# STM32G473RET6_PINOUT.net
KiCad netlist of a schematic drawn in Altium Designer
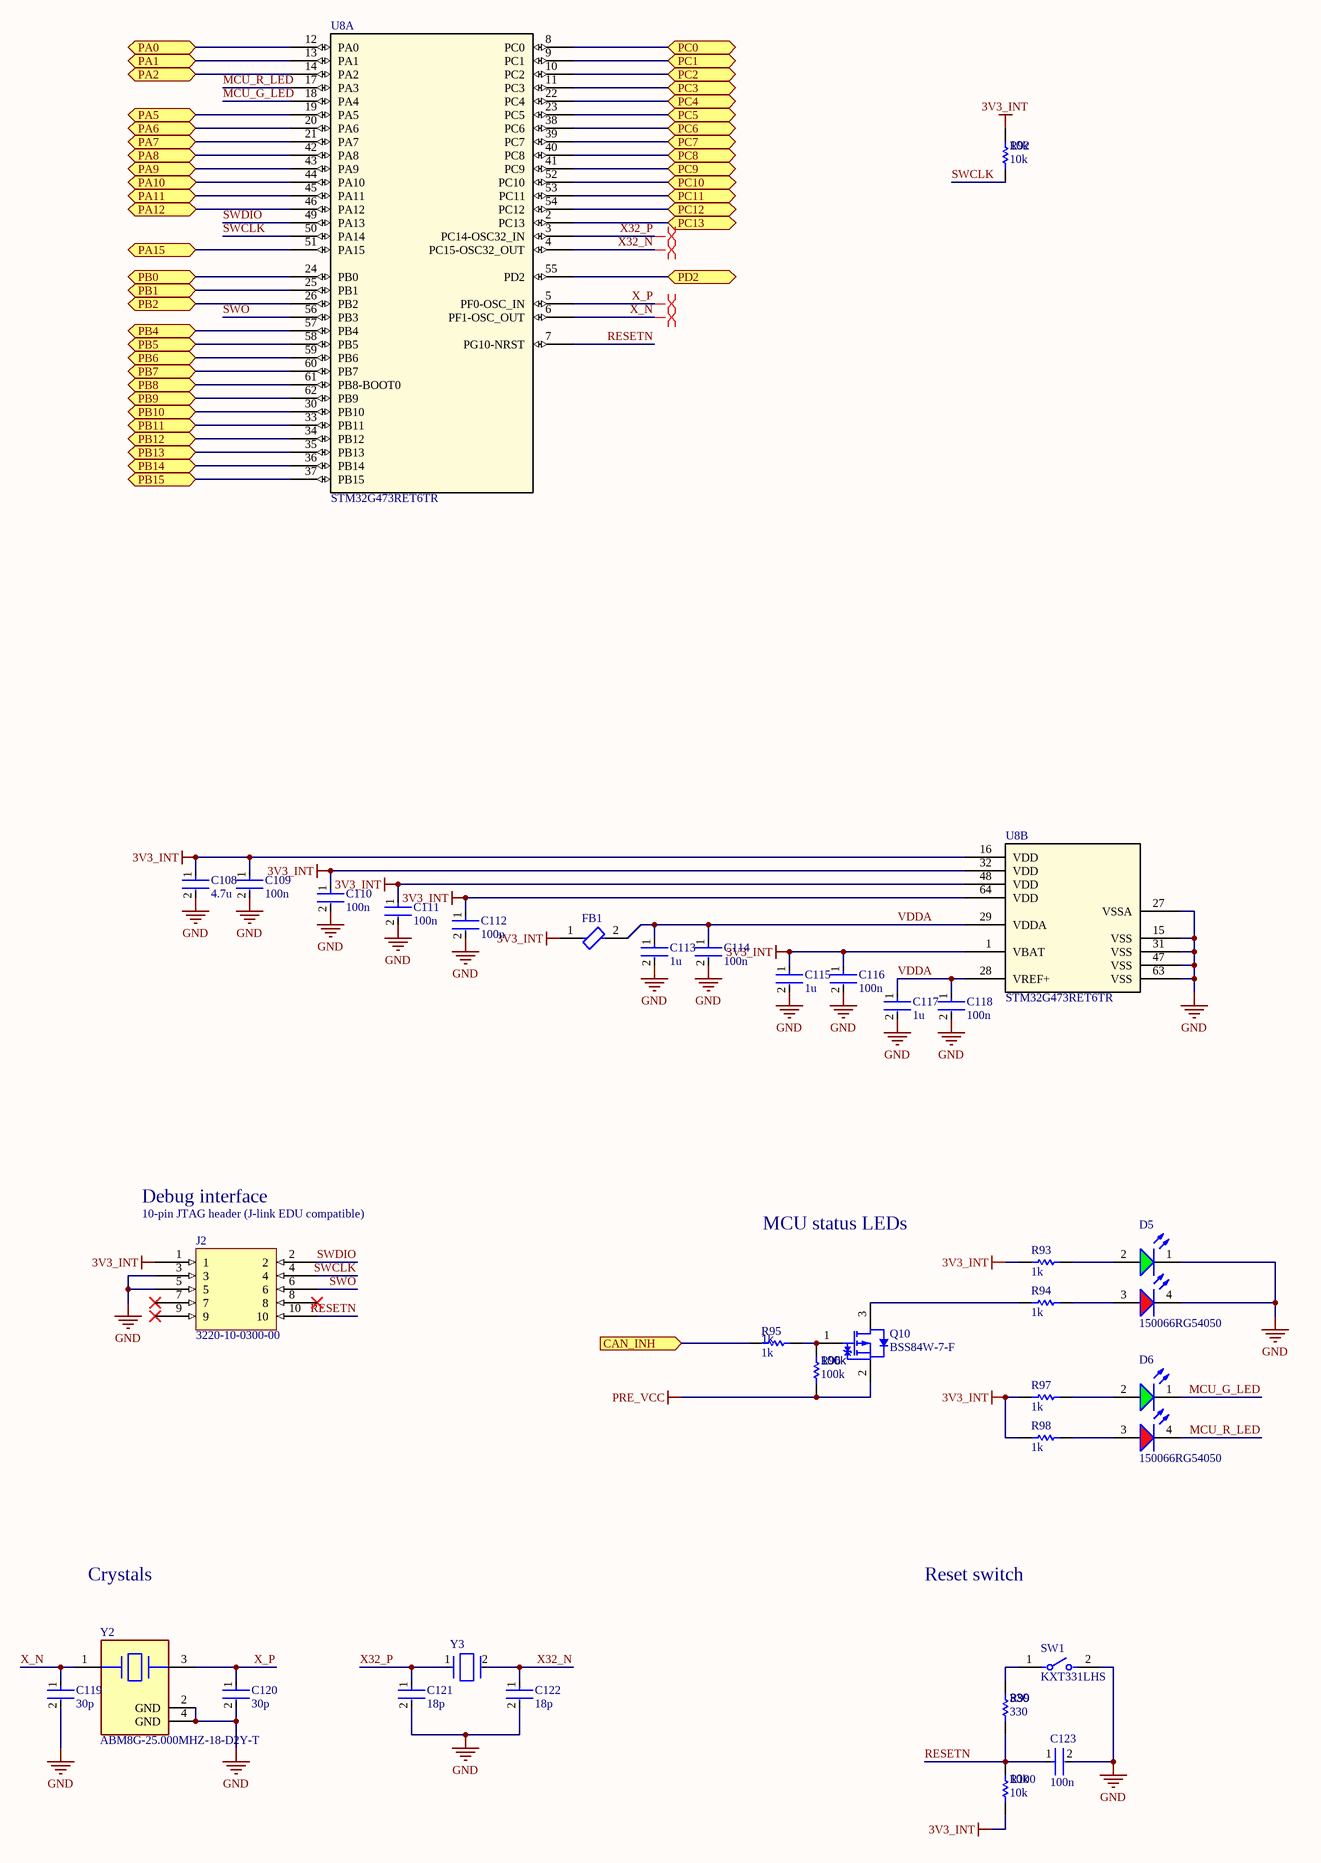
[diagram p0: STM32G473RET6_PINOUT.SchDoc]

(export (version "E")
  (design (tool "Eeschema 10.0.6"))
  (components
    (comp (ref "C108")
      (value "4.7u")
      (footprint "FP-0402-L_1_0_0_05-W_0_5-IPC_A")
      (description "LARGE PADS, 0402 CAP, CHANGE COMMENT TO MATCH REAL P/N")
      (libsource (lib "Space Concordia") (part "b4654b650e69147ec39a6b967a45e02"))
    )
    (comp (ref "C109")
      (value "100n")
      (footprint "FP-0402-L_1_0_0_05-W_0_5-IPC_A")
      (description "LARGE PADS, 0402 CAP, CHANGE COMMENT TO MATCH REAL P/N")
      (libsource (lib "Space Concordia") (part "b4654b650e69147ec39a6b967a45e02"))
    )
    (comp (ref "C110")
      (value "100n")
      (footprint "FP-0402-L_1_0_0_05-W_0_5-IPC_A")
      (description "LARGE PADS, 0402 CAP, CHANGE COMMENT TO MATCH REAL P/N")
      (libsource (lib "Space Concordia") (part "b4654b650e69147ec39a6b967a45e02"))
    )
    (comp (ref "C111")
      (value "100n")
      (footprint "FP-0402-L_1_0_0_05-W_0_5-IPC_A")
      (description "LARGE PADS, 0402 CAP, CHANGE COMMENT TO MATCH REAL P/N")
      (libsource (lib "Space Concordia") (part "b4654b650e69147ec39a6b967a45e02"))
    )
    (comp (ref "C112")
      (value "100n")
      (footprint "FP-0402-L_1_0_0_05-W_0_5-IPC_A")
      (description "LARGE PADS, 0402 CAP, CHANGE COMMENT TO MATCH REAL P/N")
      (libsource (lib "Space Concordia") (part "b4654b650e69147ec39a6b967a45e02"))
    )
    (comp (ref "C113")
      (value "1u")
      (footprint "FP-0402-L_1_0_0_05-W_0_5-IPC_A")
      (description "LARGE PADS, 0402 CAP, CHANGE COMMENT TO MATCH REAL P/N")
      (libsource (lib "Space Concordia") (part "b4654b650e69147ec39a6b967a45e02"))
    )
    (comp (ref "C114")
      (value "100n")
      (footprint "FP-0402-L_1_0_0_05-W_0_5-IPC_A")
      (description "LARGE PADS, 0402 CAP, CHANGE COMMENT TO MATCH REAL P/N")
      (libsource (lib "Space Concordia") (part "b4654b650e69147ec39a6b967a45e02"))
    )
    (comp (ref "C115")
      (value "1u")
      (footprint "FP-0402-L_1_0_0_05-W_0_5-IPC_A")
      (description "LARGE PADS, 0402 CAP, CHANGE COMMENT TO MATCH REAL P/N")
      (libsource (lib "Space Concordia") (part "b4654b650e69147ec39a6b967a45e02"))
    )
    (comp (ref "C116")
      (value "100n")
      (footprint "FP-0402-L_1_0_0_05-W_0_5-IPC_A")
      (description "LARGE PADS, 0402 CAP, CHANGE COMMENT TO MATCH REAL P/N")
      (libsource (lib "Space Concordia") (part "b4654b650e69147ec39a6b967a45e02"))
    )
    (comp (ref "C117")
      (value "1u")
      (footprint "FP-0402-L_1_0_0_05-W_0_5-IPC_A")
      (description "LARGE PADS, 0402 CAP, CHANGE COMMENT TO MATCH REAL P/N")
      (libsource (lib "Space Concordia") (part "b4654b650e69147ec39a6b967a45e02"))
    )
    (comp (ref "C118")
      (value "100n")
      (footprint "FP-0402-L_1_0_0_05-W_0_5-IPC_A")
      (description "LARGE PADS, 0402 CAP, CHANGE COMMENT TO MATCH REAL P/N")
      (libsource (lib "Space Concordia") (part "b4654b650e69147ec39a6b967a45e02"))
    )
    (comp (ref "C119")
      (value "30p")
      (footprint "FP-0402-L_1_0_0_05-W_0_5-IPC_A")
      (description "LARGE PADS, 0402 CAP, CHANGE COMMENT TO MATCH REAL P/N")
      (libsource (lib "Space Concordia") (part "b4654b650e69147ec39a6b967a45e02"))
    )
    (comp (ref "C120")
      (value "30p")
      (footprint "FP-0402-L_1_0_0_05-W_0_5-IPC_A")
      (description "LARGE PADS, 0402 CAP, CHANGE COMMENT TO MATCH REAL P/N")
      (libsource (lib "Space Concordia") (part "b4654b650e69147ec39a6b967a45e02"))
    )
    (comp (ref "C121")
      (value "18p")
      (footprint "FP-0402-L_1_0_0_05-W_0_5-IPC_A")
      (description "LARGE PADS, 0402 CAP, CHANGE COMMENT TO MATCH REAL P/N")
      (libsource (lib "Space Concordia") (part "b4654b650e69147ec39a6b967a45e02"))
    )
    (comp (ref "C122")
      (value "18p")
      (footprint "FP-0402-L_1_0_0_05-W_0_5-IPC_A")
      (description "LARGE PADS, 0402 CAP, CHANGE COMMENT TO MATCH REAL P/N")
      (libsource (lib "Space Concordia") (part "b4654b650e69147ec39a6b967a45e02"))
    )
    (comp (ref "C123")
      (value "100n")
      (footprint "FP-0402-L_1_0_0_05-W_0_5-IPC_A")
      (description "LARGE PADS, 0402 CAP, CHANGE COMMENT TO MATCH REAL P/N")
      (libsource (lib "Space Concordia") (part "b4654b650e69147ec39a6b967a45e02"))
    )
    (comp (ref "D5")
      (value "150066RG54050")
      (footprint "WL-SBCD_0606")
      (description "Led, Red/Grn, 180Mcd/230Mcd, 624Nm/525Nm Rohs Compliant: Yes")
      (fields (field (name "SOURCE") "rgled.SchLib"))
      (libsource (lib "Space Concordia") (part "CMP-004-00034-2"))
    )
    (comp (ref "D6")
      (value "150066RG54050")
      (footprint "WL-SBCD_0606")
      (description "Led, Red/Grn, 180Mcd/230Mcd, 624Nm/525Nm Rohs Compliant: Yes")
      (fields (field (name "SOURCE") "rgled.SchLib"))
      (libsource (lib "Space Concordia") (part "CMP-004-00034-2"))
    )
    (comp (ref "FB1")
      (value "BLM15PX601SN1D")
      (footprint "FP-BLM15-0_05-MFG")
      (description "Chip Ferrite Bead, 0402, 600Ω @ 100MHz, 0.23Ω, 25%, 900mA")
      (fields (field (name "TOLERANCE") "25%"))
      (libsource (lib "Altium Content Vault") (part "5f30dd21d616792df468990f7003faa"))
    )
    (comp (ref "J2")
      (value "3220-10-0300-00")
      (footprint "3220-10-0300-00-Footprint-1")
      (description "CONN HEADER SMD 10POS 1.27MM")
      (libsource (lib "Space Concordia") (part "3220-10-0300-00"))
    )
    (comp (ref "Q10")
      (value "BSS84W-7-F")
      (footprint "DIOD-SOT323-3_V")
      (fields (field (name "MANUFACTURER") "Diodes Inc"))
      (libsource (lib "Altium Content Vault") (part "PEMOS-GSD-3_C"))
    )
    (comp (ref "R92")
      (value "10k")
      (footprint "R0603B")
      (description "Resistor")
      (fields (field (name "ALTIUM_VALUE") "10k"))
      (libsource (lib "Space Concordia") (part "Resistor"))
    )
    (comp (ref "R93")
      (value "1k")
      (footprint "R0603B")
      (description "Resistor")
      (libsource (lib "Space Concordia") (part "Resistor"))
    )
    (comp (ref "R94")
      (value "1k")
      (footprint "R0603B")
      (description "Resistor")
      (libsource (lib "Space Concordia") (part "Resistor"))
    )
    (comp (ref "R95")
      (value "1k")
      (footprint "R0603B")
      (description "Resistor")
      (fields (field (name "ALTIUM_VALUE") "1k"))
      (libsource (lib "Space Concordia") (part "Resistor"))
    )
    (comp (ref "R96")
      (value "100k")
      (footprint "R0603B")
      (description "Resistor")
      (fields (field (name "ALTIUM_VALUE") "100k"))
      (libsource (lib "Space Concordia") (part "Resistor"))
    )
    (comp (ref "R97")
      (value "1k")
      (footprint "R0603B")
      (description "Resistor")
      (libsource (lib "Space Concordia") (part "Resistor"))
    )
    (comp (ref "R98")
      (value "1k")
      (footprint "R0603B")
      (description "Resistor")
      (libsource (lib "Space Concordia") (part "Resistor"))
    )
    (comp (ref "R99")
      (value "330")
      (footprint "R0603B")
      (description "Resistor")
      (fields (field (name "ALTIUM_VALUE") "330"))
      (libsource (lib "Space Concordia") (part "Resistor"))
    )
    (comp (ref "R100")
      (value "10k")
      (footprint "R0603B")
      (description "Resistor")
      (fields (field (name "ALTIUM_VALUE") "10k"))
      (libsource (lib "Space Concordia") (part "Resistor"))
    )
    (comp (ref "SW1")
      (value "KXT331LHS")
      (footprint "FP-KXT331LHS-MFG")
      (description "SWITCH TACTILE SPST-NO 0.02A 15V")
      (libsource (lib "Altium Content Vault") (part "bb27bde45df87f1f469753f287ef5ae"))
    )
    (comp (ref "U8")
      (value "STM32G473RET6TR")
      (footprint "STM32G473RET6TR-Footprint-1")
      (description "MCU 32-Bit STM32 ARM Cortex-M4 RISC 512KB Flash 1.71V to 3.6V 64-Pin LQFP T/R")
      (libsource (lib "Space Concordia") (part "STM32G473RET6TR"))
    )
    (comp (ref "Y2")
      (value "ABM8G-25.000MHZ-18-D2Y-T")
      (footprint "FP-ABM8G-MFG")
      (description "Crystal 25MHz ±20ppm (Tol) ±30ppm (Stability) 18pF FUND 60Ω 4-Pin SMD T/R")
      (fields (field (name "TOLERANCE") "20ppm"))
      (libsource (lib "Altium Content Vault") (part "48e526d86b7f2615d98721063c72f49"))
    )
    (comp (ref "Y3")
      (value "ECS-.327-12.5-1210-TR")
      (footprint "FP-ECX-1210-MFG")
      (description "CRYSTAL 32.7680KHZ 12.5PF SMD")
      (fields
        (field (name "OCTOPART") "https://octopart.com/ecs-.327-12.5-1210-tr-ecs+international-81221340")
        (field (name "TOLERANCE") "20ppm")
      )
      (libsource (lib "Altium Content Vault") (part "99724985039315a44fd0d1401b84e49"))
    )
  )
  (nets
    (net (code "1") (name "/CAN_INH") (class "Default")
      (node (ref "R95") (pin "2") (pinfunction "2_2") (pintype "passive"))
    )
    (net (code "2") (name "/MCU_G_LED") (class "Default")
      (node (ref "D6") (pin "1") (pinfunction "K_1") (pintype "passive"))
      (node (ref "U8") (pin "18") (pinfunction "PA4_18") (pintype "bidirectional"))
    )
    (net (code "3") (name "/MCU_R_LED") (class "Default")
      (node (ref "D6") (pin "4") (pinfunction "K_4") (pintype "passive"))
      (node (ref "U8") (pin "17") (pinfunction "PA3_17") (pintype "bidirectional"))
    )
    (net (code "4") (name "/PA0") (class "Default")
      (node (ref "U8") (pin "12") (pinfunction "PA0_12") (pintype "bidirectional"))
    )
    (net (code "5") (name "/PA1") (class "Default")
      (node (ref "U8") (pin "13") (pinfunction "PA1_13") (pintype "bidirectional"))
    )
    (net (code "6") (name "/PA2") (class "Default")
      (node (ref "U8") (pin "14") (pinfunction "PA2_14") (pintype "bidirectional"))
    )
    (net (code "7") (name "/PA5") (class "Default")
      (node (ref "U8") (pin "19") (pinfunction "PA5_19") (pintype "bidirectional"))
    )
    (net (code "8") (name "/PA6") (class "Default")
      (node (ref "U8") (pin "20") (pinfunction "PA6_20") (pintype "bidirectional"))
    )
    (net (code "9") (name "/PA7") (class "Default")
      (node (ref "U8") (pin "21") (pinfunction "PA7_21") (pintype "bidirectional"))
    )
    (net (code "10") (name "/PA8") (class "Default")
      (node (ref "U8") (pin "42") (pinfunction "PA8_42") (pintype "bidirectional"))
    )
    (net (code "11") (name "/PA9") (class "Default")
      (node (ref "U8") (pin "43") (pinfunction "PA9_43") (pintype "bidirectional"))
    )
    (net (code "12") (name "/PA10") (class "Default")
      (node (ref "U8") (pin "44") (pinfunction "PA10_44") (pintype "bidirectional"))
    )
    (net (code "13") (name "/PA11") (class "Default")
      (node (ref "U8") (pin "45") (pinfunction "PA11_45") (pintype "bidirectional"))
    )
    (net (code "14") (name "/PA12") (class "Default")
      (node (ref "U8") (pin "46") (pinfunction "PA12_46") (pintype "bidirectional"))
    )
    (net (code "15") (name "/PA15") (class "Default")
      (node (ref "U8") (pin "51") (pinfunction "PA15_51") (pintype "bidirectional"))
    )
    (net (code "16") (name "/PB0") (class "Default")
      (node (ref "U8") (pin "24") (pinfunction "PB0_24") (pintype "bidirectional"))
    )
    (net (code "17") (name "/PB1") (class "Default")
      (node (ref "U8") (pin "25") (pinfunction "PB1_25") (pintype "bidirectional"))
    )
    (net (code "18") (name "/PB2") (class "Default")
      (node (ref "U8") (pin "26") (pinfunction "PB2_26") (pintype "bidirectional"))
    )
    (net (code "19") (name "/PB4") (class "Default")
      (node (ref "U8") (pin "57") (pinfunction "PB4_57") (pintype "bidirectional"))
    )
    (net (code "20") (name "/PB5") (class "Default")
      (node (ref "U8") (pin "58") (pinfunction "PB5_58") (pintype "bidirectional"))
    )
    (net (code "21") (name "/PB6") (class "Default")
      (node (ref "U8") (pin "59") (pinfunction "PB6_59") (pintype "bidirectional"))
    )
    (net (code "22") (name "/PB7") (class "Default")
      (node (ref "U8") (pin "60") (pinfunction "PB7_60") (pintype "bidirectional"))
    )
    (net (code "23") (name "/PB8") (class "Default")
      (node (ref "U8") (pin "61") (pinfunction "PB8-BOOT0_61") (pintype "bidirectional"))
    )
    (net (code "24") (name "/PB9") (class "Default")
      (node (ref "U8") (pin "62") (pinfunction "PB9_62") (pintype "bidirectional"))
    )
    (net (code "25") (name "/PB10") (class "Default")
      (node (ref "U8") (pin "30") (pinfunction "PB10_30") (pintype "bidirectional"))
    )
    (net (code "26") (name "/PB11") (class "Default")
      (node (ref "U8") (pin "33") (pinfunction "PB11_33") (pintype "bidirectional"))
    )
    (net (code "27") (name "/PB12") (class "Default")
      (node (ref "U8") (pin "34") (pinfunction "PB12_34") (pintype "bidirectional"))
    )
    (net (code "28") (name "/PB13") (class "Default")
      (node (ref "U8") (pin "35") (pinfunction "PB13_35") (pintype "bidirectional"))
    )
    (net (code "29") (name "/PB14") (class "Default")
      (node (ref "U8") (pin "36") (pinfunction "PB14_36") (pintype "bidirectional"))
    )
    (net (code "30") (name "/PB15") (class "Default")
      (node (ref "U8") (pin "37") (pinfunction "PB15_37") (pintype "bidirectional"))
    )
    (net (code "31") (name "/PC0") (class "Default")
      (node (ref "U8") (pin "8") (pinfunction "PC0_8") (pintype "bidirectional"))
    )
    (net (code "32") (name "/PC1") (class "Default")
      (node (ref "U8") (pin "9") (pinfunction "PC1_9") (pintype "bidirectional"))
    )
    (net (code "33") (name "/PC2") (class "Default")
      (node (ref "U8") (pin "10") (pinfunction "PC2_10") (pintype "bidirectional"))
    )
    (net (code "34") (name "/PC3") (class "Default")
      (node (ref "U8") (pin "11") (pinfunction "PC3_11") (pintype "bidirectional"))
    )
    (net (code "35") (name "/PC4") (class "Default")
      (node (ref "U8") (pin "22") (pinfunction "PC4_22") (pintype "bidirectional"))
    )
    (net (code "36") (name "/PC5") (class "Default")
      (node (ref "U8") (pin "23") (pinfunction "PC5_23") (pintype "bidirectional"))
    )
    (net (code "37") (name "/PC6") (class "Default")
      (node (ref "U8") (pin "38") (pinfunction "PC6_38") (pintype "bidirectional"))
    )
    (net (code "38") (name "/PC7") (class "Default")
      (node (ref "U8") (pin "39") (pinfunction "PC7_39") (pintype "bidirectional"))
    )
    (net (code "39") (name "/PC8") (class "Default")
      (node (ref "U8") (pin "40") (pinfunction "PC8_40") (pintype "bidirectional"))
    )
    (net (code "40") (name "/PC9") (class "Default")
      (node (ref "U8") (pin "41") (pinfunction "PC9_41") (pintype "bidirectional"))
    )
    (net (code "41") (name "/PC10") (class "Default")
      (node (ref "U8") (pin "52") (pinfunction "PC10_52") (pintype "bidirectional"))
    )
    (net (code "42") (name "/PC11") (class "Default")
      (node (ref "U8") (pin "53") (pinfunction "PC11_53") (pintype "bidirectional"))
    )
    (net (code "43") (name "/PC12") (class "Default")
      (node (ref "U8") (pin "54") (pinfunction "PC12_54") (pintype "bidirectional"))
    )
    (net (code "44") (name "/PC13") (class "Default")
      (node (ref "U8") (pin "2") (pinfunction "PC13_2") (pintype "bidirectional"))
    )
    (net (code "45") (name "/PD2") (class "Default")
      (node (ref "U8") (pin "55") (pinfunction "PD2_55") (pintype "bidirectional"))
    )
    (net (code "46") (name "/RESETN") (class "Default")
      (node (ref "C123") (pin "1") (pinfunction "1_1") (pintype "passive"))
      (node (ref "J2") (pin "10") (pinfunction "10_10") (pintype "input"))
      (node (ref "R100") (pin "2") (pinfunction "2_2") (pintype "passive"))
      (node (ref "R99") (pin "1") (pinfunction "1_1") (pintype "passive"))
      (node (ref "U8") (pin "7") (pinfunction "PG10-NRST_7") (pintype "bidirectional"))
    )
    (net (code "47") (name "/SWCLK") (class "Default")
      (node (ref "J2") (pin "4") (pinfunction "4_4") (pintype "input"))
      (node (ref "R92") (pin "1") (pinfunction "1_1") (pintype "passive"))
      (node (ref "U8") (pin "50") (pinfunction "PA14_50") (pintype "bidirectional"))
    )
    (net (code "48") (name "/SWDIO") (class "Default")
      (node (ref "J2") (pin "2") (pinfunction "2_2") (pintype "input"))
      (node (ref "U8") (pin "49") (pinfunction "PA13_49") (pintype "bidirectional"))
    )
    (net (code "49") (name "/SWO") (class "Default")
      (node (ref "J2") (pin "6") (pinfunction "6_6") (pintype "input"))
      (node (ref "U8") (pin "56") (pinfunction "PB3_56") (pintype "bidirectional"))
    )
    (net (code "50") (name "/VDDA") (class "Default")
      (node (ref "C113") (pin "1") (pinfunction "1_1") (pintype "passive"))
      (node (ref "C114") (pin "1") (pinfunction "1_1") (pintype "passive"))
      (node (ref "C117") (pin "1") (pinfunction "1_1") (pintype "passive"))
      (node (ref "C118") (pin "1") (pinfunction "1_1") (pintype "passive"))
      (node (ref "FB1") (pin "2") (pinfunction "2_2") (pintype "passive"))
      (node (ref "U8") (pin "28") (pinfunction "VREF+_28") (pintype "power_in"))
      (node (ref "U8") (pin "29") (pinfunction "VDDA_29") (pintype "power_in"))
    )
    (net (code "51") (name "/X32_N") (class "Default")
      (node (ref "C122") (pin "1") (pinfunction "1_1") (pintype "passive"))
      (node (ref "U8") (pin "4") (pinfunction "PC15-OSC32_OUT_4") (pintype "bidirectional"))
      (node (ref "Y3") (pin "2") (pinfunction "Out/In_2") (pintype "passive"))
    )
    (net (code "52") (name "/X32_P") (class "Default")
      (node (ref "C121") (pin "1") (pinfunction "1_1") (pintype "passive"))
      (node (ref "U8") (pin "3") (pinfunction "PC14-OSC32_IN_3") (pintype "bidirectional"))
      (node (ref "Y3") (pin "1") (pinfunction "In/Out_1") (pintype "passive"))
    )
    (net (code "53") (name "/X_N") (class "Default")
      (node (ref "C119") (pin "1") (pinfunction "1_1") (pintype "passive"))
      (node (ref "U8") (pin "6") (pinfunction "PF1-OSC_OUT_6") (pintype "bidirectional"))
      (node (ref "Y2") (pin "1") (pinfunction "1_1") (pintype "passive"))
    )
    (net (code "54") (name "/X_P") (class "Default")
      (node (ref "C120") (pin "1") (pinfunction "1_1") (pintype "passive"))
      (node (ref "U8") (pin "5") (pinfunction "PF0-OSC_IN_5") (pintype "bidirectional"))
      (node (ref "Y2") (pin "3") (pinfunction "3_3") (pintype "passive"))
    )
    (net (code "55") (name "3V3_INT") (class "Default")
      (node (ref "C108") (pin "1") (pinfunction "1_1") (pintype "passive"))
      (node (ref "C109") (pin "1") (pinfunction "1_1") (pintype "passive"))
      (node (ref "C110") (pin "1") (pinfunction "1_1") (pintype "passive"))
      (node (ref "C111") (pin "1") (pinfunction "1_1") (pintype "passive"))
      (node (ref "C112") (pin "1") (pinfunction "1_1") (pintype "passive"))
      (node (ref "C115") (pin "1") (pinfunction "1_1") (pintype "passive"))
      (node (ref "C116") (pin "1") (pinfunction "1_1") (pintype "passive"))
      (node (ref "FB1") (pin "1") (pinfunction "1_1") (pintype "passive"))
      (node (ref "J2") (pin "1") (pinfunction "1_1") (pintype "input"))
      (node (ref "R100") (pin "1") (pinfunction "1_1") (pintype "passive"))
      (node (ref "R92") (pin "2") (pinfunction "2_2") (pintype "passive"))
      (node (ref "R93") (pin "2") (pinfunction "2_2") (pintype "passive"))
      (node (ref "R97") (pin "2") (pinfunction "2_2") (pintype "passive"))
      (node (ref "R98") (pin "2") (pinfunction "2_2") (pintype "passive"))
      (node (ref "U8") (pin "1") (pinfunction "VBAT_1") (pintype "power_in"))
      (node (ref "U8") (pin "16") (pinfunction "VDD_16") (pintype "power_in"))
      (node (ref "U8") (pin "32") (pinfunction "VDD_32") (pintype "power_in"))
      (node (ref "U8") (pin "48") (pinfunction "VDD_48") (pintype "power_in"))
      (node (ref "U8") (pin "64") (pinfunction "VDD_64") (pintype "power_in"))
    )
    (net (code "56") (name "GND") (class "Default")
      (node (ref "C108") (pin "2") (pinfunction "2_2") (pintype "passive"))
      (node (ref "C109") (pin "2") (pinfunction "2_2") (pintype "passive"))
      (node (ref "C110") (pin "2") (pinfunction "2_2") (pintype "passive"))
      (node (ref "C111") (pin "2") (pinfunction "2_2") (pintype "passive"))
      (node (ref "C112") (pin "2") (pinfunction "2_2") (pintype "passive"))
      (node (ref "C113") (pin "2") (pinfunction "2_2") (pintype "passive"))
      (node (ref "C114") (pin "2") (pinfunction "2_2") (pintype "passive"))
      (node (ref "C115") (pin "2") (pinfunction "2_2") (pintype "passive"))
      (node (ref "C116") (pin "2") (pinfunction "2_2") (pintype "passive"))
      (node (ref "C117") (pin "2") (pinfunction "2_2") (pintype "passive"))
      (node (ref "C118") (pin "2") (pinfunction "2_2") (pintype "passive"))
      (node (ref "C119") (pin "2") (pinfunction "2_2") (pintype "passive"))
      (node (ref "C120") (pin "2") (pinfunction "2_2") (pintype "passive"))
      (node (ref "C121") (pin "2") (pinfunction "2_2") (pintype "passive"))
      (node (ref "C122") (pin "2") (pinfunction "2_2") (pintype "passive"))
      (node (ref "C123") (pin "2") (pinfunction "2_2") (pintype "passive"))
      (node (ref "D5") (pin "1") (pinfunction "K_1") (pintype "passive"))
      (node (ref "D5") (pin "4") (pinfunction "K_4") (pintype "passive"))
      (node (ref "J2") (pin "3") (pinfunction "3_3") (pintype "input"))
      (node (ref "J2") (pin "5") (pinfunction "5_5") (pintype "input"))
      (node (ref "SW1") (pin "2") (pinfunction "2_2") (pintype "passive"))
      (node (ref "U8") (pin "15") (pinfunction "VSS_15") (pintype "power_in"))
      (node (ref "U8") (pin "27") (pinfunction "VSSA_27") (pintype "power_in"))
      (node (ref "U8") (pin "31") (pinfunction "VSS_31") (pintype "power_in"))
      (node (ref "U8") (pin "47") (pinfunction "VSS_47") (pintype "power_in"))
      (node (ref "U8") (pin "63") (pinfunction "VSS_63") (pintype "power_in"))
      (node (ref "Y2") (pin "2") (pinfunction "GND_2") (pintype "power_in"))
      (node (ref "Y2") (pin "4") (pinfunction "GND_4") (pintype "power_in"))
    )
    (net (code "57") (name "Net-(D5-A-Pad2)") (class "Default")
      (node (ref "D5") (pin "2") (pinfunction "A_2") (pintype "passive"))
      (node (ref "R93") (pin "1") (pinfunction "1_1") (pintype "passive"))
    )
    (net (code "58") (name "Net-(D5-A-Pad3)") (class "Default")
      (node (ref "D5") (pin "3") (pinfunction "A_3") (pintype "passive"))
      (node (ref "R94") (pin "1") (pinfunction "1_1") (pintype "passive"))
    )
    (net (code "59") (name "Net-(D6-A-Pad2)") (class "Default")
      (node (ref "D6") (pin "2") (pinfunction "A_2") (pintype "passive"))
      (node (ref "R97") (pin "1") (pinfunction "1_1") (pintype "passive"))
    )
    (net (code "60") (name "Net-(D6-A-Pad3)") (class "Default")
      (node (ref "D6") (pin "3") (pinfunction "A_3") (pintype "passive"))
      (node (ref "R98") (pin "1") (pinfunction "1_1") (pintype "passive"))
    )
    (net (code "61") (name "Net-(Q10-D)") (class "Default")
      (node (ref "Q10") (pin "3") (pinfunction "D_3") (pintype "passive"))
      (node (ref "R94") (pin "2") (pinfunction "2_2") (pintype "passive"))
    )
    (net (code "62") (name "Net-(Q10-G)") (class "Default")
      (node (ref "Q10") (pin "1") (pinfunction "G_1") (pintype "passive"))
      (node (ref "R95") (pin "1") (pinfunction "1_1") (pintype "passive"))
      (node (ref "R96") (pin "1") (pinfunction "1_1") (pintype "passive"))
    )
    (net (code "63") (name "Net-(R99-Pad2)") (class "Default")
      (node (ref "R99") (pin "2") (pinfunction "2_2") (pintype "passive"))
      (node (ref "SW1") (pin "1") (pinfunction "1_1") (pintype "passive"))
    )
    (net (code "64") (name "PRE_VCC") (class "Default")
      (node (ref "Q10") (pin "2") (pinfunction "S_2") (pintype "passive"))
      (node (ref "R96") (pin "2") (pinfunction "2_2") (pintype "passive"))
    )
    (net (code "65") (name "unconnected-(J2-Pad7)") (class "Default")
      (node (ref "J2") (pin "7") (pinfunction "7_7") (pintype "input+no_connect"))
    )
    (net (code "66") (name "unconnected-(J2-Pad8)") (class "Default")
      (node (ref "J2") (pin "8") (pinfunction "8_8") (pintype "input+no_connect"))
    )
    (net (code "67") (name "unconnected-(J2-Pad9)") (class "Default")
      (node (ref "J2") (pin "9") (pinfunction "9_9") (pintype "input+no_connect"))
    )
  )
)
